# OBC_V1.net
KiCad netlist of a schematic drawn in Altium Designer
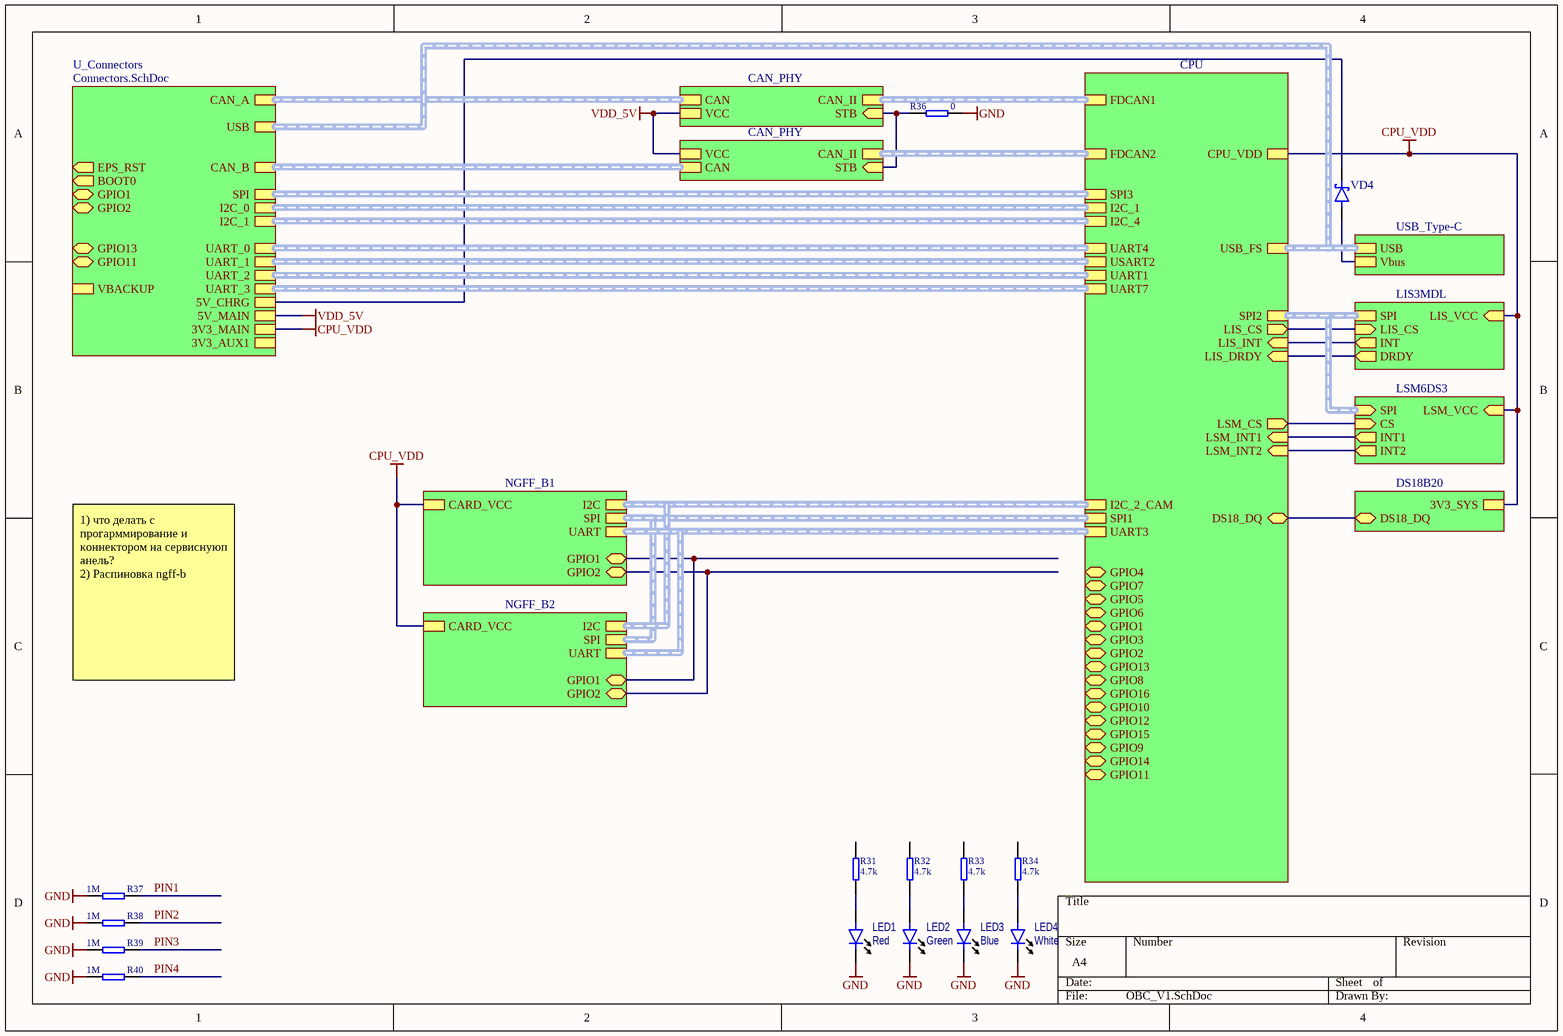
[diagram p0: OBC_V1.SchDoc]

(export (version "E")
  (design (tool "Eeschema 10.0.6"))
  (components
    (comp (ref "LED1")
      (value "Red")
      (footprint "LED 0805")
      (description "Light Emittering Diode")
      (fields (field (name "Comment") "LED 0805 Red"))
      (libsource (lib "!main") (part "LED"))
    )
    (comp (ref "LED2")
      (value "Green")
      (footprint "LED 0805")
      (description "Light Emittering Diode")
      (fields (field (name "Comment") "LED 0805 Green"))
      (libsource (lib "!main") (part "LED"))
    )
    (comp (ref "LED3")
      (value "Blue")
      (footprint "LED 0805")
      (description "Light Emittering Diode")
      (fields (field (name "Comment") "LED 0805 Blue"))
      (libsource (lib "!main") (part "LED"))
    )
    (comp (ref "LED4")
      (value "White")
      (footprint "LED 0805")
      (description "Light Emittering Diode")
      (fields (field (name "Comment") "LED 0805 White"))
      (libsource (lib "!main") (part "LED"))
    )
    (comp (ref "R31")
      (value "4.7k")
      (footprint "RES 0603")
      (description "Resistor")
      (fields (field (name "Comment") "RES 0603 4.7k"))
      (libsource (lib "!main") (part "!Resistor"))
    )
    (comp (ref "R32")
      (value "4.7k")
      (footprint "RES 0603")
      (description "Resistor")
      (fields (field (name "Comment") "RES 0603 4.7k"))
      (libsource (lib "!main") (part "!Resistor"))
    )
    (comp (ref "R33")
      (value "4.7k")
      (footprint "RES 0603")
      (description "Resistor")
      (fields (field (name "Comment") "RES 0603 4.7k"))
      (libsource (lib "!main") (part "!Resistor"))
    )
    (comp (ref "R34")
      (value "4.7k")
      (footprint "RES 0603")
      (description "Resistor")
      (fields (field (name "Comment") "RES 0603 4.7k"))
      (libsource (lib "!main") (part "!Resistor"))
    )
    (comp (ref "R36")
      (value "0")
      (footprint "RES 0603")
      (description "Resistor")
      (fields (field (name "Comment") "RES 0603 0"))
      (libsource (lib "!main") (part "!Resistor"))
    )
    (comp (ref "R37")
      (value "1M")
      (footprint "RES 0402")
      (description "Resistor")
      (fields (field (name "Comment") "RES 0402 1M"))
      (libsource (lib "!main") (part "!Resistor"))
    )
    (comp (ref "R38")
      (value "1M")
      (footprint "RES 0402")
      (description "Resistor")
      (fields (field (name "Comment") "RES 0402 1M"))
      (libsource (lib "!main") (part "!Resistor"))
    )
    (comp (ref "R39")
      (value "1M")
      (footprint "RES 0402")
      (description "Resistor")
      (fields (field (name "Comment") "RES 0402 1M"))
      (libsource (lib "!main") (part "!Resistor"))
    )
    (comp (ref "R40")
      (value "1M")
      (footprint "RES 0402")
      (description "Resistor")
      (fields (field (name "Comment") "RES 0402 1M"))
      (libsource (lib "!main") (part "!Resistor"))
    )
    (comp (ref "VD4")
      (value "Shottly diode SOD-123")
      (footprint "SOD-123")
      (description "Diode Shottky")
      (libsource (lib "diodes") (part "DiodeS"))
    )
  )
  (nets
    (net (code "2") (name "/5V_CHRG") (class "Default")
      (node (ref "VD4") (pin "C") (pinfunction "Cathode_C") (pintype "passive"))
    )
    (net (code "41") (name "/PIN1") (class "Default")
      (node (ref "R37") (pin "2") (pinfunction "12_2") (pintype "passive"))
    )
    (net (code "42") (name "/PIN2") (class "Default")
      (node (ref "R38") (pin "2") (pinfunction "12_2") (pintype "passive"))
    )
    (net (code "43") (name "/PIN3") (class "Default")
      (node (ref "R39") (pin "2") (pinfunction "12_2") (pintype "passive"))
    )
    (net (code "44") (name "/PIN4") (class "Default")
      (node (ref "R40") (pin "2") (pinfunction "12_2") (pintype "passive"))
    )
    (net (code "48") (name "/STB") (class "Default")
      (node (ref "R36") (pin "1") (pinfunction "11_1") (pintype "passive"))
    )
    (net (code "56") (name "/Vbus") (class "Default")
      (node (ref "VD4") (pin "A") (pinfunction "Anode_A") (pintype "passive"))
    )
    (net (code "58") (name "GND") (class "Default")
      (node (ref "LED1") (pin "2") (pinfunction "Cathode_2") (pintype "passive"))
      (node (ref "LED2") (pin "2") (pinfunction "Cathode_2") (pintype "passive"))
      (node (ref "LED3") (pin "2") (pinfunction "Cathode_2") (pintype "passive"))
      (node (ref "LED4") (pin "2") (pinfunction "Cathode_2") (pintype "passive"))
      (node (ref "R36") (pin "2") (pinfunction "12_2") (pintype "passive"))
      (node (ref "R37") (pin "1") (pinfunction "11_1") (pintype "passive"))
      (node (ref "R38") (pin "1") (pinfunction "11_1") (pintype "passive"))
      (node (ref "R39") (pin "1") (pinfunction "11_1") (pintype "passive"))
      (node (ref "R40") (pin "1") (pinfunction "11_1") (pintype "passive"))
    )
    (net (code "59") (name "Net-(LED1-Anode)") (class "Default")
      (node (ref "LED1") (pin "1") (pinfunction "Anode_1") (pintype "passive"))
      (node (ref "R31") (pin "1") (pinfunction "11_1") (pintype "passive"))
    )
    (net (code "60") (name "Net-(LED2-Anode)") (class "Default")
      (node (ref "LED2") (pin "1") (pinfunction "Anode_1") (pintype "passive"))
      (node (ref "R32") (pin "1") (pinfunction "11_1") (pintype "passive"))
    )
    (net (code "61") (name "Net-(LED3-Anode)") (class "Default")
      (node (ref "LED3") (pin "1") (pinfunction "Anode_1") (pintype "passive"))
      (node (ref "R33") (pin "1") (pinfunction "11_1") (pintype "passive"))
    )
    (net (code "62") (name "Net-(LED4-Anode)") (class "Default")
      (node (ref "LED4") (pin "1") (pinfunction "Anode_1") (pintype "passive"))
      (node (ref "R34") (pin "1") (pinfunction "11_1") (pintype "passive"))
    )
    (net (code "64") (name "unconnected-(R31-12-Pad2)") (class "Default")
      (node (ref "R31") (pin "2") (pinfunction "12_2") (pintype "passive"))
    )
    (net (code "65") (name "unconnected-(R32-12-Pad2)") (class "Default")
      (node (ref "R32") (pin "2") (pinfunction "12_2") (pintype "passive"))
    )
    (net (code "66") (name "unconnected-(R33-12-Pad2)") (class "Default")
      (node (ref "R33") (pin "2") (pinfunction "12_2") (pintype "passive"))
    )
    (net (code "67") (name "unconnected-(R34-12-Pad2)") (class "Default")
      (node (ref "R34") (pin "2") (pinfunction "12_2") (pintype "passive"))
    )
  )
)
